# eeprom.net
KiCad netlist of a schematic drawn in Altium Designer
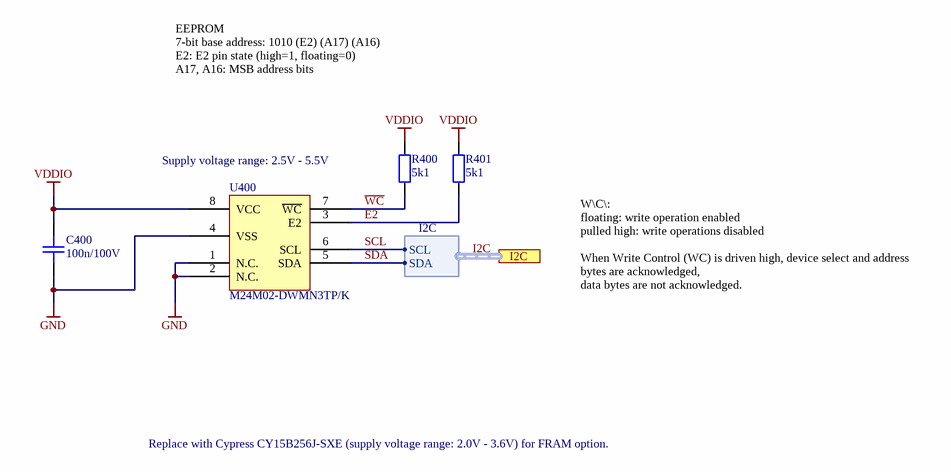
[diagram p0: eeprom.SchDoc]

(export (version "E")
  (design (tool "Eeschema 10.0.6"))
  (components
    (comp (ref "C400")
      (value "100n/100V")
      (footprint "CAPC1608X08N")
      (description "MLCC")
      (fields (field (name "PART NUMBER") "gen_C_ceramic_100n_100V_X7R_0603"))
      (libsource (lib "OE750") (part "C"))
    )
    (comp (ref "R400")
      (value "5k1")
      (footprint "RESC1608X05N")
      (description "SMD Resistor 5k1 0603")
      (fields (field (name "PART NUMBER") "gen_R_5k1_0603") (field (name "TOLERANCE") "5%"))
      (libsource (lib "OE750") (part "R"))
    )
    (comp (ref "R401")
      (value "5k1")
      (footprint "RESC1608X05N")
      (description "SMD Resistor 5k1 0603")
      (fields (field (name "PART NUMBER") "gen_R_5k1_0603") (field (name "POWER") "0.1W"))
      (libsource (lib "OE750") (part "R"))
    )
    (comp (ref "U400")
      (value "M24M02-DWMN3TP/K")
      (footprint "SOIC127P600X175-8N")
      (description "Automotive 2-Mbit serial I²C \r\nbus EEPROM with 1 MHz clock")
      (fields (field (name "MANUFACTURER") "STMicroelectronics"))
      (libsource (lib "OE750") (part "M24M02-DWMN3TP/K"))
    )
  )
  (nets
    (net (code "2") (name "/E2") (class "Default")
      (node (ref "R401") (pin "1") (pinfunction "1_1") (pintype "passive"))
      (node (ref "U400") (pin "3") (pinfunction "E2_3") (pintype "passive"))
    )
    (net (code "4") (name "/SCL") (class "Default")
      (node (ref "U400") (pin "6") (pinfunction "SCL_6") (pintype "passive"))
    )
    (net (code "5") (name "/SDA") (class "Default")
      (node (ref "U400") (pin "5") (pinfunction "SDA_5") (pintype "passive"))
    )
    (net (code "6") (name "/~{WC}") (class "Default")
      (node (ref "R400") (pin "1") (pinfunction "1_1") (pintype "passive"))
      (node (ref "U400") (pin "7") (pinfunction "~{WC}_7") (pintype "passive"))
    )
    (net (code "7") (name "GND") (class "Default")
      (node (ref "C400") (pin "1") (pinfunction "1_1") (pintype "passive"))
      (node (ref "U400") (pin "1") (pinfunction "N.C._1") (pintype "passive"))
      (node (ref "U400") (pin "2") (pinfunction "N.C._2") (pintype "passive"))
      (node (ref "U400") (pin "4") (pinfunction "VSS_4") (pintype "power_in"))
    )
    (net (code "8") (name "VDDIO") (class "Default")
      (node (ref "C400") (pin "2") (pinfunction "2_2") (pintype "passive"))
      (node (ref "R400") (pin "2") (pinfunction "2_2") (pintype "passive"))
      (node (ref "R401") (pin "2") (pinfunction "2_2") (pintype "passive"))
      (node (ref "U400") (pin "8") (pinfunction "VCC_8") (pintype "power_in"))
    )
  )
)
